# 06_STM43F4_UART.net
KiCad netlist of a schematic drawn in Altium Designer
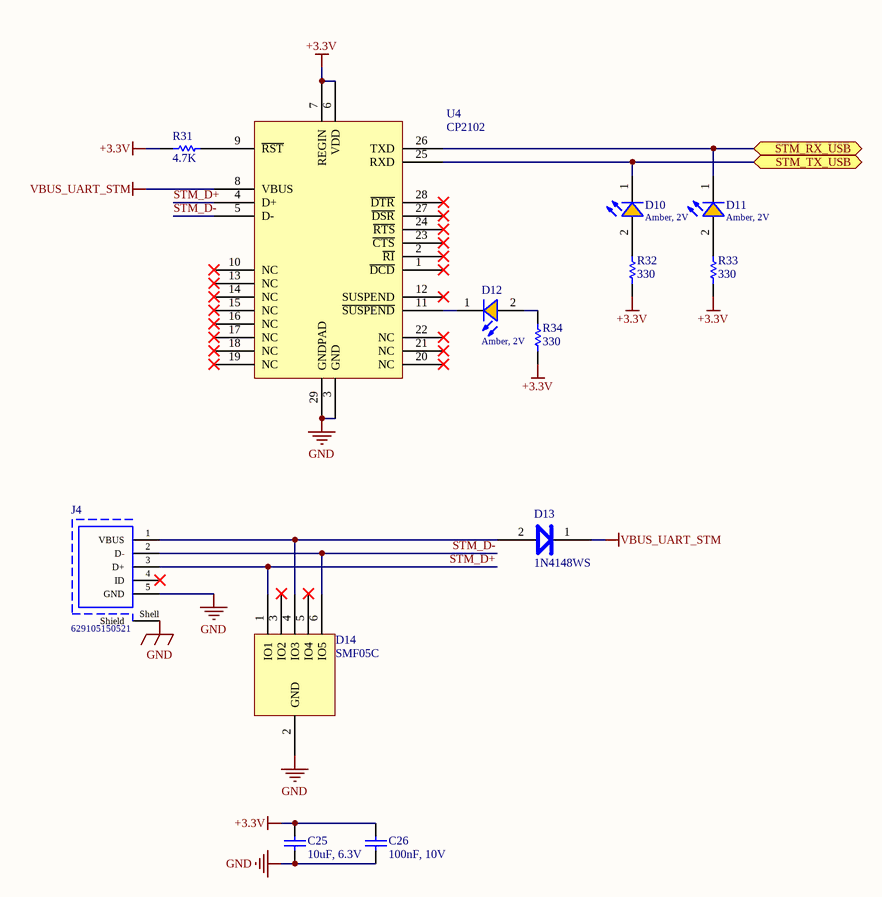
[diagram p0: 06_STM43F4_UART.SchDoc]

(export (version "E")
  (design (tool "Eeschema 10.0.6"))
  (components
    (comp (ref "C25")
      (value "10uF, 6.3V")
      (footprint "WCAP-CSGP_0603_H=0.8mm_Reflow")
      (description "WCAP-CSGP Multilayer Ceramic Chip Capacitor, General Purpose, size 0603, X5R, 10uF, 6.3V")
      (fields
        (field (name "MANUFACTURER PART NUMBER") "885012106006")
        (field (name "MANUFACTURER") "Wurth Elektronik")
      )
      (libsource (lib "Altium_WCAP-CSGP (rev20a)") (part "885012106006"))
    )
    (comp (ref "C26")
      (value "100nF, 10V")
      (footprint "WCAP-CSGP_0603_H=0.8mm_Reflow")
      (description "WCAP-CSGP Multilayer Ceramic Chip Capacitor, General Purpose, size 0603, X7R, 100nF, 10V")
      (fields
        (field (name "MANUFACTURER PART NUMBER") "885012206020")
        (field (name "MANUFACTURER") "Wurth Elektronik")
      )
      (libsource (lib "Altium_WCAP-CSGP (rev20a)") (part "885012206020"))
    )
    (comp (ref "D10")
      (value "Amber, 2V")
      (footprint "WL-SMCW_0603_H=0.7mm")
      (description "WL-SMCW SMT Mono-color Chip LED Waterclear, size 0603, Amber, 2V, 140deg")
      (fields (field (name "PART NUMBER") "150060AS75000") (field (name "PUBLISHER") "Wurth Elektronik"))
      (libsource (lib "Altium_WL-SMCW (rev20a)") (part "150060AS75000"))
    )
    (comp (ref "D11")
      (value "Amber, 2V")
      (footprint "WL-SMCW_0603_H=0.7mm")
      (description "WL-SMCW SMT Mono-color Chip LED Waterclear, size 0603, Amber, 2V, 140deg")
      (fields (field (name "PART NUMBER") "150060AS75000") (field (name "PUBLISHER") "Wurth Elektronik"))
      (libsource (lib "Altium_WL-SMCW (rev20a)") (part "150060AS75000"))
    )
    (comp (ref "D12")
      (value "Amber, 2V")
      (footprint "WL-SMCW_0603_H=0.7mm")
      (description "WL-SMCW SMT Mono-color Chip LED Waterclear, size 0603, Amber, 2V, 140deg")
      (fields (field (name "PART NUMBER") "150060AS75000") (field (name "PUBLISHER") "Wurth Elektronik"))
      (libsource (lib "Altium_WL-SMCW (rev20a)") (part "150060AS75000"))
    )
    (comp (ref "D13")
      (value "1N4148WS")
      (footprint "SODFL250X90-2N")
      (libsource (lib "MiclsLib") (part "1N4148WS"))
    )
    (comp (ref "D14")
      (value "SMF05C")
      (footprint "SOT65P210X110-6N")
      (libsource (lib "MiclsLib") (part "SMF05C"))
    )
    (comp (ref "J4")
      (value "629105150521")
      (footprint "629105150521")
      (description "Micro USB 2.0 Type B Receptacle WR-COM, Horizontal, SMT, with Pegs, High Current at Pin 1 & Pin 5")
      (fields (field (name "PUBLISHER") "Wurth Elektronik"))
      (libsource (lib "ALTIUM-WR-COM_USB_20-rev18d") (part "629105150521"))
    )
    (comp (ref "R31")
      (value "4.7K")
      (footprint "RES-SM-0603")
      (description "Resistor")
      (fields (field (name "Comment") "RESISTOR SMD"))
      (libsource (lib "PIF_Library") (part "RESISTOR SMD"))
    )
    (comp (ref "R32")
      (value "330")
      (footprint "RES-SM-0603")
      (description "Resistor")
      (fields (field (name "Comment") "RESISTOR SMD"))
      (libsource (lib "PIF_Library") (part "RESISTOR SMD"))
    )
    (comp (ref "R33")
      (value "330")
      (footprint "RES-SM-0603")
      (description "Resistor")
      (fields (field (name "Comment") "RESISTOR SMD"))
      (libsource (lib "PIF_Library") (part "RESISTOR SMD"))
    )
    (comp (ref "R34")
      (value "330")
      (footprint "RES-SM-0603")
      (description "Resistor")
      (fields (field (name "Comment") "RESISTOR SMD"))
      (libsource (lib "PIF_Library") (part "RESISTOR SMD"))
    )
    (comp (ref "U4")
      (value "CP2102")
      (footprint "QFN50P500X500X90_HS-29N")
      (libsource (lib "MiclsLib") (part "CP2102"))
    )
  )
  (nets
    (net (code "1") (name "+3.3V") (class "Default")
      (node (ref "C25") (pin "2") (pinfunction "2_2") (pintype "passive"))
      (node (ref "C26") (pin "2") (pinfunction "2_2") (pintype "passive"))
      (node (ref "R31") (pin "2") (pinfunction "2_2") (pintype "passive"))
      (node (ref "R32") (pin "2") (pinfunction "2_2") (pintype "passive"))
      (node (ref "R33") (pin "2") (pinfunction "2_2") (pintype "passive"))
      (node (ref "R34") (pin "2") (pinfunction "2_2") (pintype "passive"))
      (node (ref "U4") (pin "6") (pinfunction "VDD_6") (pintype "passive"))
      (node (ref "U4") (pin "7") (pinfunction "REGIN_7") (pintype "passive"))
    )
    (net (code "2") (name "/STM_D+") (class "Default")
      (node (ref "D14") (pin "1") (pinfunction "IO1_1") (pintype "passive"))
      (node (ref "J4") (pin "3") (pinfunction "D+_3") (pintype "passive"))
      (node (ref "U4") (pin "4") (pinfunction "D+_4") (pintype "passive"))
    )
    (net (code "3") (name "/STM_D-") (class "Default")
      (node (ref "D14") (pin "6") (pinfunction "IO5_6") (pintype "passive"))
      (node (ref "J4") (pin "2") (pinfunction "D-_2") (pintype "passive"))
      (node (ref "U4") (pin "5") (pinfunction "D-_5") (pintype "passive"))
    )
    (net (code "4") (name "/STM_RX_USB") (class "Default")
      (node (ref "D11") (pin "1") (pinfunction "K_1") (pintype "passive"))
      (node (ref "U4") (pin "26") (pinfunction "TXD_26") (pintype "passive"))
    )
    (net (code "5") (name "/STM_TX_USB") (class "Default")
      (node (ref "D10") (pin "1") (pinfunction "K_1") (pintype "passive"))
      (node (ref "U4") (pin "25") (pinfunction "RXD_25") (pintype "passive"))
    )
    (net (code "6") (name "GND") (class "Default")
      (node (ref "C25") (pin "1") (pinfunction "1_1") (pintype "passive"))
      (node (ref "C26") (pin "1") (pinfunction "1_1") (pintype "passive"))
      (node (ref "D14") (pin "2") (pinfunction "GND_2") (pintype "passive"))
      (node (ref "J4") (pin "5") (pinfunction "GND_5") (pintype "passive"))
      (node (ref "J4") (pin "Shell") (pinfunction "Shield_Shell") (pintype "passive"))
      (node (ref "U4") (pin "29") (pinfunction "GNDPAD_29") (pintype "passive"))
      (node (ref "U4") (pin "3") (pinfunction "GND_3") (pintype "passive"))
    )
    (net (code "7") (name "Net-(D10-A)") (class "Default")
      (node (ref "D10") (pin "2") (pinfunction "A_2") (pintype "passive"))
      (node (ref "R32") (pin "1") (pinfunction "1_1") (pintype "passive"))
    )
    (net (code "8") (name "Net-(D11-A)") (class "Default")
      (node (ref "D11") (pin "2") (pinfunction "A_2") (pintype "passive"))
      (node (ref "R33") (pin "1") (pinfunction "1_1") (pintype "passive"))
    )
    (net (code "9") (name "Net-(D12-A)") (class "Default")
      (node (ref "D12") (pin "2") (pinfunction "A_2") (pintype "passive"))
      (node (ref "R34") (pin "1") (pinfunction "1_1") (pintype "passive"))
    )
    (net (code "10") (name "Net-(D12-K)") (class "Default")
      (node (ref "D12") (pin "1") (pinfunction "K_1") (pintype "passive"))
      (node (ref "U4") (pin "11") (pinfunction "~{SUSPEND}_11") (pintype "passive"))
    )
    (net (code "11") (name "Net-(D14-IO3)") (class "Default")
      (node (ref "D13") (pin "2") (pinfunction "2_2") (pintype "passive"))
      (node (ref "D14") (pin "4") (pinfunction "IO3_4") (pintype "passive"))
      (node (ref "J4") (pin "1") (pinfunction "VBUS_1") (pintype "passive"))
    )
    (net (code "12") (name "Net-(U4-~{RST})") (class "Default")
      (node (ref "R31") (pin "1") (pinfunction "1_1") (pintype "passive"))
      (node (ref "U4") (pin "9") (pinfunction "~{RST}_9") (pintype "passive"))
    )
    (net (code "13") (name "VBUS_UART_STM") (class "Default")
      (node (ref "D13") (pin "1") (pinfunction "1_1") (pintype "passive"))
      (node (ref "U4") (pin "8") (pinfunction "VBUS_8") (pintype "passive"))
    )
    (net (code "14") (name "unconnected-(D14-IO2-Pad3)") (class "Default")
      (node (ref "D14") (pin "3") (pinfunction "IO2_3") (pintype "passive+no_connect"))
    )
    (net (code "15") (name "unconnected-(D14-IO4-Pad5)") (class "Default")
      (node (ref "D14") (pin "5") (pinfunction "IO4_5") (pintype "passive+no_connect"))
    )
    (net (code "16") (name "unconnected-(J4-ID-Pad4)") (class "Default")
      (node (ref "J4") (pin "4") (pinfunction "ID_4") (pintype "passive+no_connect"))
    )
    (net (code "17") (name "unconnected-(U4-NC-Pad10)") (class "Default")
      (node (ref "U4") (pin "10") (pinfunction "NC_10") (pintype "passive+no_connect"))
    )
    (net (code "18") (name "unconnected-(U4-NC-Pad13)") (class "Default")
      (node (ref "U4") (pin "13") (pinfunction "NC_13") (pintype "passive+no_connect"))
    )
    (net (code "19") (name "unconnected-(U4-NC-Pad14)") (class "Default")
      (node (ref "U4") (pin "14") (pinfunction "NC_14") (pintype "passive+no_connect"))
    )
    (net (code "20") (name "unconnected-(U4-NC-Pad15)") (class "Default")
      (node (ref "U4") (pin "15") (pinfunction "NC_15") (pintype "passive+no_connect"))
    )
    (net (code "21") (name "unconnected-(U4-NC-Pad16)") (class "Default")
      (node (ref "U4") (pin "16") (pinfunction "NC_16") (pintype "passive+no_connect"))
    )
    (net (code "22") (name "unconnected-(U4-NC-Pad17)") (class "Default")
      (node (ref "U4") (pin "17") (pinfunction "NC_17") (pintype "passive+no_connect"))
    )
    (net (code "23") (name "unconnected-(U4-NC-Pad18)") (class "Default")
      (node (ref "U4") (pin "18") (pinfunction "NC_18") (pintype "passive+no_connect"))
    )
    (net (code "24") (name "unconnected-(U4-NC-Pad19)") (class "Default")
      (node (ref "U4") (pin "19") (pinfunction "NC_19") (pintype "passive+no_connect"))
    )
    (net (code "25") (name "unconnected-(U4-NC-Pad20)") (class "Default")
      (node (ref "U4") (pin "20") (pinfunction "NC_20") (pintype "passive+no_connect"))
    )
    (net (code "26") (name "unconnected-(U4-NC-Pad21)") (class "Default")
      (node (ref "U4") (pin "21") (pinfunction "NC_21") (pintype "passive+no_connect"))
    )
    (net (code "27") (name "unconnected-(U4-NC-Pad22)") (class "Default")
      (node (ref "U4") (pin "22") (pinfunction "NC_22") (pintype "passive+no_connect"))
    )
    (net (code "28") (name "unconnected-(U4-SUSPEND-Pad12)") (class "Default")
      (node (ref "U4") (pin "12") (pinfunction "SUSPEND_12") (pintype "passive+no_connect"))
    )
    (net (code "29") (name "unconnected-(U4-~{CTS}-Pad23)") (class "Default")
      (node (ref "U4") (pin "23") (pinfunction "~{CTS}_23") (pintype "passive+no_connect"))
    )
    (net (code "30") (name "unconnected-(U4-~{DCD}-Pad1)") (class "Default")
      (node (ref "U4") (pin "1") (pinfunction "~{DCD}_1") (pintype "passive+no_connect"))
    )
    (net (code "31") (name "unconnected-(U4-~{DSR}-Pad27)") (class "Default")
      (node (ref "U4") (pin "27") (pinfunction "~{DSR}_27") (pintype "passive+no_connect"))
    )
    (net (code "32") (name "unconnected-(U4-~{DTR}-Pad28)") (class "Default")
      (node (ref "U4") (pin "28") (pinfunction "~{DTR}_28") (pintype "passive+no_connect"))
    )
    (net (code "33") (name "unconnected-(U4-~{RI}-Pad2)") (class "Default")
      (node (ref "U4") (pin "2") (pinfunction "~{RI}_2") (pintype "passive+no_connect"))
    )
    (net (code "34") (name "unconnected-(U4-~{RTS}-Pad24)") (class "Default")
      (node (ref "U4") (pin "24") (pinfunction "~{RTS}_24") (pintype "passive+no_connect"))
    )
  )
)
